# PWM_control.net
KiCad netlist of a schematic drawn in Altium Designer
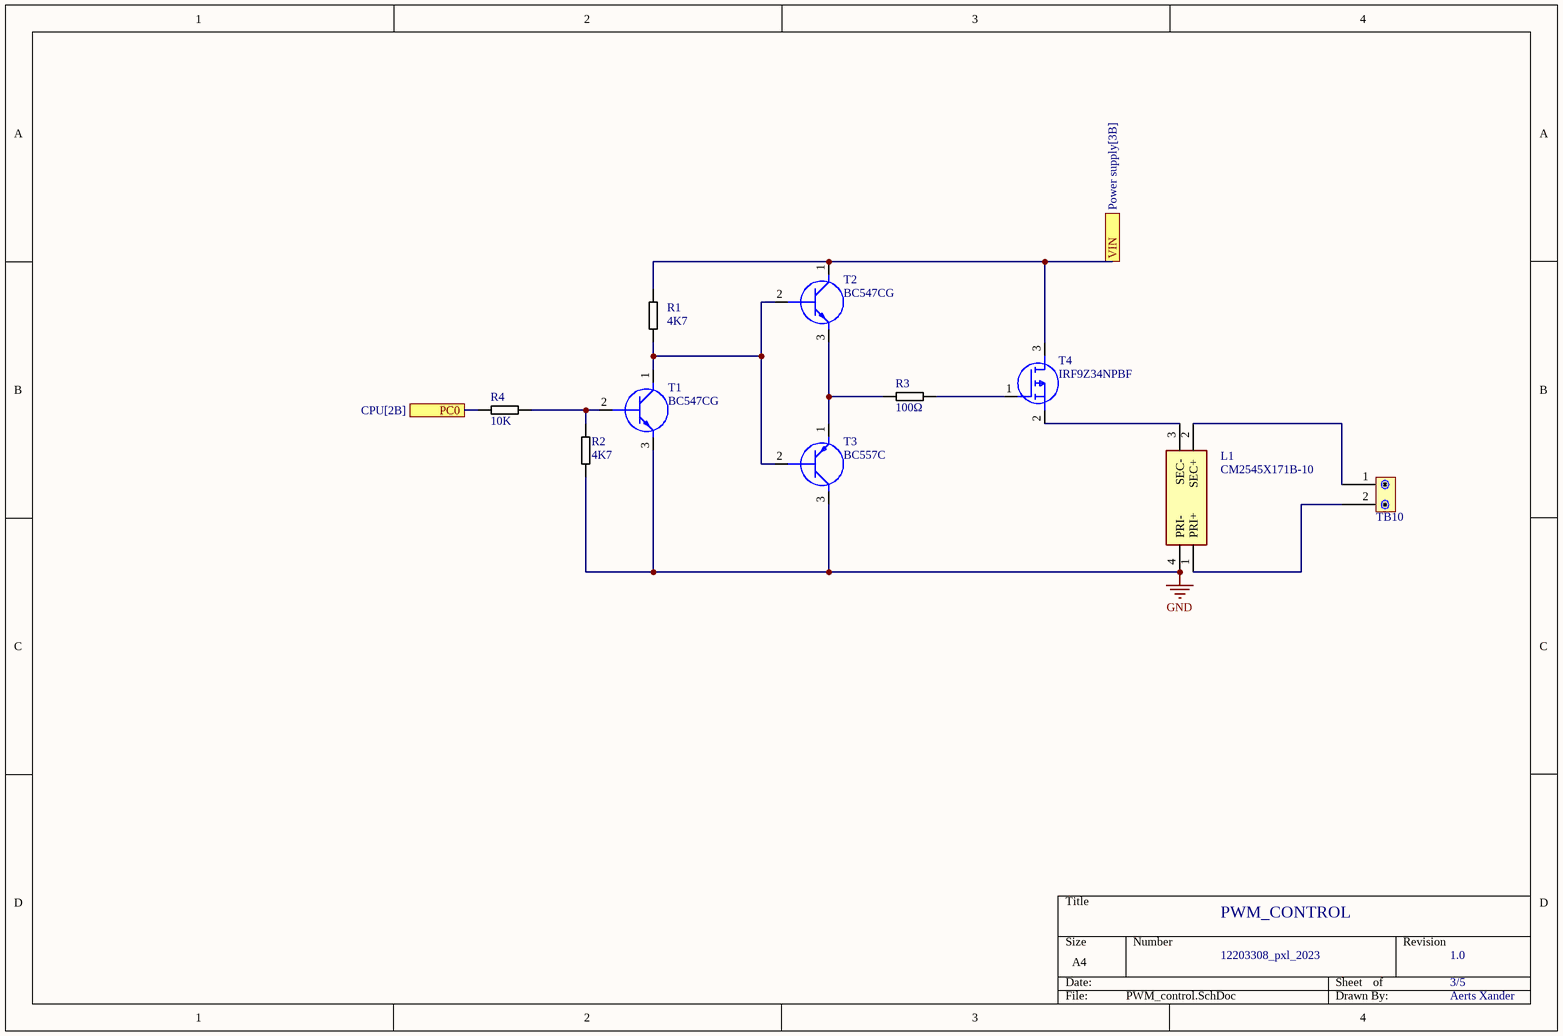
[diagram p0: PWM_control.SchDoc]

(export (version "E")
  (design (tool "Eeschema 10.0.6"))
  (components
    (comp (ref "L1")
      (value "CM2545X171B-10")
      (footprint "CM2545X171B-10")
      (description "Transformer")
      (libsource (lib "soldeerstation") (part "CM2545X171B-10"))
    )
    (comp (ref "R1")
      (value "4K7")
      (footprint "0805")
      (fields (field (name "MANUFACTURER") "Vishay Dale") (field (name "PART NUMBER") "CRCW08050000Z0EA"))
      (libsource (lib "soldeerstation") (part "resistor"))
    )
    (comp (ref "R2")
      (value "4K7")
      (footprint "0805")
      (fields (field (name "MANUFACTURER") "Vishay Dale") (field (name "PART NUMBER") "CRCW08050000Z0EA"))
      (libsource (lib "soldeerstation") (part "resistor"))
    )
    (comp (ref "R3")
      (value "100Ω")
      (footprint "0805")
      (fields (field (name "MANUFACTURER") "Vishay Dale") (field (name "PART NUMBER") "CRCW08050000Z0EA"))
      (libsource (lib "soldeerstation") (part "resistor"))
    )
    (comp (ref "R4")
      (value "10K")
      (footprint "0805")
      (fields (field (name "MANUFACTURER") "Vishay Dale") (field (name "PART NUMBER") "CRCW08050000Z0EA"))
      (libsource (lib "soldeerstation") (part "resistor"))
    )
    (comp (ref "T1")
      (value "BC547CG")
      (footprint "BC547CG")
      (description "Transistor BJT NPN")
      (fields (field (name "MOUSER PART NUMBER") "863-BC547CG"))
      (libsource (lib "soldeerstation") (part "BC547CG"))
    )
    (comp (ref "T2")
      (value "BC547CG")
      (footprint "BC547CG")
      (description "Transistor BJT NPN")
      (fields (field (name "MOUSER PART NUMBER") "863-BC547CG"))
      (libsource (lib "soldeerstation") (part "BC547CG"))
    )
    (comp (ref "T3")
      (value "BC557C")
      (footprint "BC557C")
      (description "Transistor BJT PNP")
      (fields (field (name "MOUSER PART NUMBER") "771-BC557C"))
      (libsource (lib "soldeerstation") (part "BC557C"))
    )
    (comp (ref "T4")
      (value "IRF9Z34NPBF")
      (footprint "IRF9Z34NPBF")
      (description "MOSFET (P-Channel)")
      (fields (field (name "MOUSER PART NUMBER") "942-IRF9Z34NPBF"))
      (libsource (lib "soldeerstation") (part "IRF9Z34NPBF"))
    )
    (comp (ref "TB10")
      (value "2pin screw connector")
      (footprint "2pin screw connector")
      (libsource (lib "soldeerstation") (part "2pin screw connector"))
    )
  )
  (nets
    (net (code "1") (name "/PC0") (class "Default")
      (node (ref "R4") (pin "2") (pinfunction "2_2") (pintype "passive"))
    )
    (net (code "2") (name "/VIN") (class "Default")
      (node (ref "R1") (pin "2") (pinfunction "2_2") (pintype "passive"))
      (node (ref "T2") (pin "1") (pinfunction "C_1") (pintype "passive"))
      (node (ref "T4") (pin "3") (pinfunction "D_3") (pintype "passive"))
    )
    (net (code "3") (name "GND") (class "Default")
      (node (ref "L1") (pin "4") (pinfunction "PRI-_4") (pintype "passive"))
      (node (ref "R2") (pin "1") (pinfunction "1_1") (pintype "passive"))
      (node (ref "T1") (pin "3") (pinfunction "E_3") (pintype "passive"))
      (node (ref "T3") (pin "3") (pinfunction "C_3") (pintype "passive"))
    )
    (net (code "4") (name "Net-(L1-PRI+)") (class "Default")
      (node (ref "L1") (pin "1") (pinfunction "PRI+_1") (pintype "passive"))
      (node (ref "TB10") (pin "2") (pinfunction "30_2") (pintype "passive"))
    )
    (net (code "5") (name "Net-(L1-SEC+)") (class "Default")
      (node (ref "L1") (pin "2") (pinfunction "SEC+_2") (pintype "passive"))
      (node (ref "TB10") (pin "1") (pinfunction "29_1") (pintype "passive"))
    )
    (net (code "6") (name "Net-(L1-SEC-)") (class "Default")
      (node (ref "L1") (pin "3") (pinfunction "SEC-_3") (pintype "passive"))
      (node (ref "T4") (pin "2") (pinfunction "S_2") (pintype "passive"))
    )
    (net (code "7") (name "Net-(T1-B)") (class "Default")
      (node (ref "R2") (pin "2") (pinfunction "2_2") (pintype "passive"))
      (node (ref "R4") (pin "1") (pinfunction "1_1") (pintype "passive"))
      (node (ref "T1") (pin "2") (pinfunction "B_2") (pintype "passive"))
    )
    (net (code "8") (name "Net-(T1-C)") (class "Default")
      (node (ref "R1") (pin "1") (pinfunction "1_1") (pintype "passive"))
      (node (ref "T1") (pin "1") (pinfunction "C_1") (pintype "passive"))
      (node (ref "T2") (pin "2") (pinfunction "B_2") (pintype "passive"))
      (node (ref "T3") (pin "2") (pinfunction "B_2") (pintype "passive"))
    )
    (net (code "9") (name "Net-(T2-E)") (class "Default")
      (node (ref "R3") (pin "2") (pinfunction "2_2") (pintype "passive"))
      (node (ref "T2") (pin "3") (pinfunction "E_3") (pintype "passive"))
      (node (ref "T3") (pin "1") (pinfunction "E_1") (pintype "passive"))
    )
    (net (code "10") (name "Net-(T4-G)") (class "Default")
      (node (ref "R3") (pin "1") (pinfunction "1_1") (pintype "passive"))
      (node (ref "T4") (pin "1") (pinfunction "G_1") (pintype "passive"))
    )
  )
)
